# StompBoard.net
KiCad netlist of a schematic drawn in EAGLE
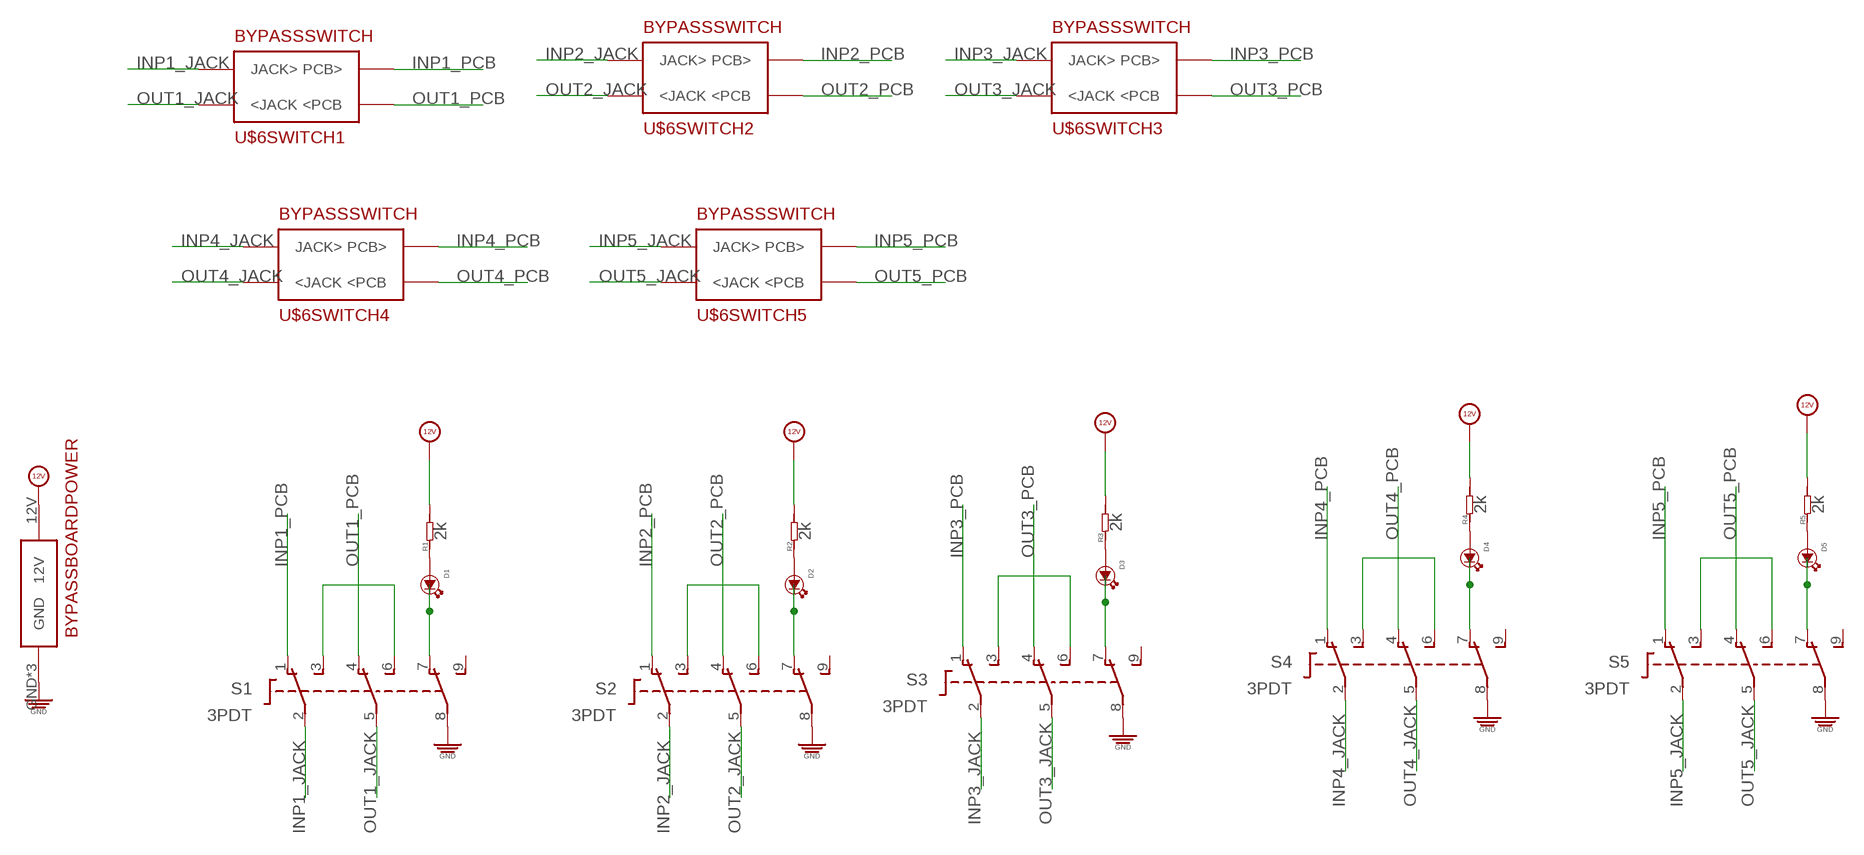
[diagram p0: schematic, sheet 1]

(export (version "E")
  (design (tool "Eeschema 10.0.6"))
  (components
    (comp (ref "D1")
      (value "LED3MM")
      (footprint "eagle-import:3MMLED")
      (libsource (lib "eagle-import") (part "LED3MM"))
    )
    (comp (ref "D2")
      (value "LED3MM")
      (footprint "eagle-import:3MMLED")
      (libsource (lib "eagle-import") (part "LED3MM"))
    )
    (comp (ref "D3")
      (value "LED3MM")
      (footprint "eagle-import:3MMLED")
      (libsource (lib "eagle-import") (part "LED3MM"))
    )
    (comp (ref "D4")
      (value "LED3MM")
      (footprint "eagle-import:3MMLED")
      (libsource (lib "eagle-import") (part "LED3MM"))
    )
    (comp (ref "D5")
      (value "LED3MM")
      (footprint "eagle-import:3MMLED")
      (libsource (lib "eagle-import") (part "LED3MM"))
    )
    (comp (ref "R1")
      (value "2k")
      (footprint "eagle-import:R0603")
      (libsource (lib "eagle-import") (part "R-0603"))
    )
    (comp (ref "R2")
      (value "2k")
      (footprint "eagle-import:R0603")
      (libsource (lib "eagle-import") (part "R-0603"))
    )
    (comp (ref "R3")
      (value "2k")
      (footprint "eagle-import:R0603")
      (libsource (lib "eagle-import") (part "R-0603"))
    )
    (comp (ref "R4")
      (value "2k")
      (footprint "eagle-import:R0603")
      (libsource (lib "eagle-import") (part "R-0603"))
    )
    (comp (ref "R5")
      (value "2k")
      (footprint "eagle-import:R0603")
      (libsource (lib "eagle-import") (part "R-0603"))
    )
    (comp (ref "S1")
      (value "3PDT")
      (footprint "eagle-import:3PDT")
      (libsource (lib "eagle-import") (part "3PDT"))
    )
    (comp (ref "S2")
      (value "3PDT")
      (footprint "eagle-import:3PDT")
      (libsource (lib "eagle-import") (part "3PDT"))
    )
    (comp (ref "S3")
      (value "3PDT")
      (footprint "eagle-import:3PDT")
      (libsource (lib "eagle-import") (part "3PDT"))
    )
    (comp (ref "S4")
      (value "3PDT")
      (footprint "eagle-import:3PDT")
      (libsource (lib "eagle-import") (part "3PDT"))
    )
    (comp (ref "S5")
      (value "3PDT")
      (footprint "eagle-import:3PDT")
      (libsource (lib "eagle-import") (part "3PDT"))
    )
    (comp (ref "U$6")
      (value "5STOMPBOARD")
      (footprint "eagle-import:BYPASSBOARD")
      (libsource (lib "eagle-import") (part "5STOMPBOARD"))
    )
  )
  (nets
    (net (code "1") (name "/INP1_JACK") (class "Default")
      (node (ref "S1") (pin "2") (pinfunction "P1_2") (pintype "passive"))
      (node (ref "U$6") (pin "P$3") (pinfunction "JACK>_P$3") (pintype "bidirectional"))
    )
    (net (code "2") (name "/INP1_PCB") (class "Default")
      (node (ref "S1") (pin "1") (pinfunction "O1_1") (pintype "passive"))
      (node (ref "U$6") (pin "P$4") (pinfunction "PCB>_P$4") (pintype "bidirectional"))
    )
    (net (code "3") (name "/INP2_JACK") (class "Default")
      (node (ref "S2") (pin "2") (pinfunction "P1_2") (pintype "passive"))
      (node (ref "U$6") (pin "P$7") (pinfunction "JACK>_P$7") (pintype "bidirectional"))
    )
    (net (code "4") (name "/INP2_PCB") (class "Default")
      (node (ref "S2") (pin "1") (pinfunction "O1_1") (pintype "passive"))
      (node (ref "U$6") (pin "P$8") (pinfunction "PCB>_P$8") (pintype "bidirectional"))
    )
    (net (code "5") (name "/INP3_JACK") (class "Default")
      (node (ref "S3") (pin "2") (pinfunction "P1_2") (pintype "passive"))
      (node (ref "U$6") (pin "P$11") (pinfunction "JACK>_P$11") (pintype "bidirectional"))
    )
    (net (code "6") (name "/INP3_PCB") (class "Default")
      (node (ref "S3") (pin "1") (pinfunction "O1_1") (pintype "passive"))
      (node (ref "U$6") (pin "P$12") (pinfunction "PCB>_P$12") (pintype "bidirectional"))
    )
    (net (code "7") (name "/INP4_JACK") (class "Default")
      (node (ref "S4") (pin "2") (pinfunction "P1_2") (pintype "passive"))
      (node (ref "U$6") (pin "P$15") (pinfunction "JACK>_P$15") (pintype "bidirectional"))
    )
    (net (code "8") (name "/INP4_PCB") (class "Default")
      (node (ref "S4") (pin "1") (pinfunction "O1_1") (pintype "passive"))
      (node (ref "U$6") (pin "P$16") (pinfunction "PCB>_P$16") (pintype "bidirectional"))
    )
    (net (code "9") (name "/INP5_JACK") (class "Default")
      (node (ref "S5") (pin "2") (pinfunction "P1_2") (pintype "passive"))
      (node (ref "U$6") (pin "P$19") (pinfunction "JACK>_P$19") (pintype "bidirectional"))
    )
    (net (code "10") (name "/INP5_PCB") (class "Default")
      (node (ref "S5") (pin "1") (pinfunction "O1_1") (pintype "passive"))
      (node (ref "U$6") (pin "P$20") (pinfunction "PCB>_P$20") (pintype "bidirectional"))
    )
    (net (code "11") (name "/OUT1_JACK") (class "Default")
      (node (ref "S1") (pin "5") (pinfunction "P2_5") (pintype "passive"))
      (node (ref "U$6") (pin "P$1") (pinfunction "<JACK_P$1") (pintype "bidirectional"))
    )
    (net (code "12") (name "/OUT1_PCB") (class "Default")
      (node (ref "S1") (pin "4") (pinfunction "O2_4") (pintype "passive"))
      (node (ref "U$6") (pin "P$2") (pinfunction "<PCB_P$2") (pintype "bidirectional"))
    )
    (net (code "13") (name "/OUT2_JACK") (class "Default")
      (node (ref "S2") (pin "5") (pinfunction "P2_5") (pintype "passive"))
      (node (ref "U$6") (pin "P$5") (pinfunction "<JACK_P$5") (pintype "bidirectional"))
    )
    (net (code "14") (name "/OUT2_PCB") (class "Default")
      (node (ref "S2") (pin "4") (pinfunction "O2_4") (pintype "passive"))
      (node (ref "U$6") (pin "P$6") (pinfunction "<PCB_P$6") (pintype "bidirectional"))
    )
    (net (code "15") (name "/OUT3_JACK") (class "Default")
      (node (ref "S3") (pin "5") (pinfunction "P2_5") (pintype "passive"))
      (node (ref "U$6") (pin "P$9") (pinfunction "<JACK_P$9") (pintype "bidirectional"))
    )
    (net (code "16") (name "/OUT3_PCB") (class "Default")
      (node (ref "S3") (pin "4") (pinfunction "O2_4") (pintype "passive"))
      (node (ref "U$6") (pin "P$10") (pinfunction "<PCB_P$10") (pintype "bidirectional"))
    )
    (net (code "17") (name "/OUT4_JACK") (class "Default")
      (node (ref "S4") (pin "5") (pinfunction "P2_5") (pintype "passive"))
      (node (ref "U$6") (pin "P$13") (pinfunction "<JACK_P$13") (pintype "bidirectional"))
    )
    (net (code "18") (name "/OUT4_PCB") (class "Default")
      (node (ref "S4") (pin "4") (pinfunction "O2_4") (pintype "passive"))
      (node (ref "U$6") (pin "P$14") (pinfunction "<PCB_P$14") (pintype "bidirectional"))
    )
    (net (code "19") (name "/OUT5_JACK") (class "Default")
      (node (ref "S5") (pin "5") (pinfunction "P2_5") (pintype "passive"))
      (node (ref "U$6") (pin "P$17") (pinfunction "<JACK_P$17") (pintype "bidirectional"))
    )
    (net (code "20") (name "/OUT5_PCB") (class "Default")
      (node (ref "S5") (pin "4") (pinfunction "O2_4") (pintype "passive"))
      (node (ref "U$6") (pin "P$18") (pinfunction "<PCB_P$18") (pintype "bidirectional"))
    )
    (net (code "21") (name "12V") (class "Default")
      (node (ref "R1") (pin "2") (pinfunction "2_2") (pintype "bidirectional"))
      (node (ref "R2") (pin "2") (pinfunction "2_2") (pintype "bidirectional"))
      (node (ref "R3") (pin "2") (pinfunction "2_2") (pintype "bidirectional"))
      (node (ref "R4") (pin "2") (pinfunction "2_2") (pintype "bidirectional"))
      (node (ref "R5") (pin "2") (pinfunction "2_2") (pintype "bidirectional"))
      (node (ref "U$6") (pin "12V") (pinfunction "12V_12V") (pintype "bidirectional"))
    )
    (net (code "22") (name "GND") (class "Default")
      (node (ref "S1") (pin "8") (pinfunction "P3_8") (pintype "passive"))
      (node (ref "S2") (pin "8") (pinfunction "P3_8") (pintype "passive"))
      (node (ref "S3") (pin "8") (pinfunction "P3_8") (pintype "passive"))
      (node (ref "S4") (pin "8") (pinfunction "P3_8") (pintype "passive"))
      (node (ref "S5") (pin "8") (pinfunction "P3_8") (pintype "passive"))
      (node (ref "U$6") (pin "GND") (pinfunction "GND_GND") (pintype "bidirectional"))
      (node (ref "U$6") (pin "GND2") (pinfunction "GND_GND2") (pintype "bidirectional"))
      (node (ref "U$6") (pin "GND3") (pinfunction "GND_GND3") (pintype "bidirectional"))
    )
    (net (code "23") (name "Net-(D1-Pad+)") (class "Default")
      (node (ref "D1") (pin "+") (pinfunction "+_+") (pintype "passive"))
      (node (ref "R1") (pin "1") (pinfunction "1_1") (pintype "bidirectional"))
    )
    (net (code "24") (name "Net-(D2-Pad+)") (class "Default")
      (node (ref "D2") (pin "+") (pinfunction "+_+") (pintype "passive"))
      (node (ref "R2") (pin "1") (pinfunction "1_1") (pintype "bidirectional"))
    )
    (net (code "25") (name "Net-(D3-Pad+)") (class "Default")
      (node (ref "D3") (pin "+") (pinfunction "+_+") (pintype "passive"))
      (node (ref "R3") (pin "1") (pinfunction "1_1") (pintype "bidirectional"))
    )
    (net (code "26") (name "Net-(D4-Pad+)") (class "Default")
      (node (ref "D4") (pin "+") (pinfunction "+_+") (pintype "passive"))
      (node (ref "R4") (pin "1") (pinfunction "1_1") (pintype "bidirectional"))
    )
    (net (code "27") (name "Net-(D5-Pad+)") (class "Default")
      (node (ref "D5") (pin "+") (pinfunction "+_+") (pintype "passive"))
      (node (ref "R5") (pin "1") (pinfunction "1_1") (pintype "bidirectional"))
    )
    (net (code "28") (name "Net-(S1-O3)") (class "Default")
      (node (ref "D1") (pin "-") (pinfunction "-_-") (pintype "passive"))
      (node (ref "S1") (pin "7") (pinfunction "O3_7") (pintype "passive"))
    )
    (net (code "29") (name "Net-(S1-S1)") (class "Default")
      (node (ref "S1") (pin "3") (pinfunction "S1_3") (pintype "passive"))
      (node (ref "S1") (pin "6") (pinfunction "S2_6") (pintype "passive"))
    )
    (net (code "30") (name "Net-(S2-O3)") (class "Default")
      (node (ref "D2") (pin "-") (pinfunction "-_-") (pintype "passive"))
      (node (ref "S2") (pin "7") (pinfunction "O3_7") (pintype "passive"))
    )
    (net (code "31") (name "Net-(S2-S1)") (class "Default")
      (node (ref "S2") (pin "3") (pinfunction "S1_3") (pintype "passive"))
      (node (ref "S2") (pin "6") (pinfunction "S2_6") (pintype "passive"))
    )
    (net (code "32") (name "Net-(S3-O3)") (class "Default")
      (node (ref "D3") (pin "-") (pinfunction "-_-") (pintype "passive"))
      (node (ref "S3") (pin "7") (pinfunction "O3_7") (pintype "passive"))
    )
    (net (code "33") (name "Net-(S3-S1)") (class "Default")
      (node (ref "S3") (pin "3") (pinfunction "S1_3") (pintype "passive"))
      (node (ref "S3") (pin "6") (pinfunction "S2_6") (pintype "passive"))
    )
    (net (code "34") (name "Net-(S4-O3)") (class "Default")
      (node (ref "D4") (pin "-") (pinfunction "-_-") (pintype "passive"))
      (node (ref "S4") (pin "7") (pinfunction "O3_7") (pintype "passive"))
    )
    (net (code "35") (name "Net-(S4-S1)") (class "Default")
      (node (ref "S4") (pin "3") (pinfunction "S1_3") (pintype "passive"))
      (node (ref "S4") (pin "6") (pinfunction "S2_6") (pintype "passive"))
    )
    (net (code "36") (name "Net-(S5-O3)") (class "Default")
      (node (ref "D5") (pin "-") (pinfunction "-_-") (pintype "passive"))
      (node (ref "S5") (pin "7") (pinfunction "O3_7") (pintype "passive"))
    )
    (net (code "37") (name "Net-(S5-S1)") (class "Default")
      (node (ref "S5") (pin "3") (pinfunction "S1_3") (pintype "passive"))
      (node (ref "S5") (pin "6") (pinfunction "S2_6") (pintype "passive"))
    )
    (net (code "38") (name "unconnected-(S1-S3-Pad9)") (class "Default")
      (node (ref "S1") (pin "9") (pinfunction "S3_9") (pintype "passive"))
    )
    (net (code "39") (name "unconnected-(S2-S3-Pad9)") (class "Default")
      (node (ref "S2") (pin "9") (pinfunction "S3_9") (pintype "passive"))
    )
    (net (code "40") (name "unconnected-(S3-S3-Pad9)") (class "Default")
      (node (ref "S3") (pin "9") (pinfunction "S3_9") (pintype "passive"))
    )
    (net (code "41") (name "unconnected-(S4-S3-Pad9)") (class "Default")
      (node (ref "S4") (pin "9") (pinfunction "S3_9") (pintype "passive"))
    )
    (net (code "42") (name "unconnected-(S5-S3-Pad9)") (class "Default")
      (node (ref "S5") (pin "9") (pinfunction "S3_9") (pintype "passive"))
    )
  )
)
